# TopLevel.net
KiCad netlist of a schematic drawn in Altium Designer
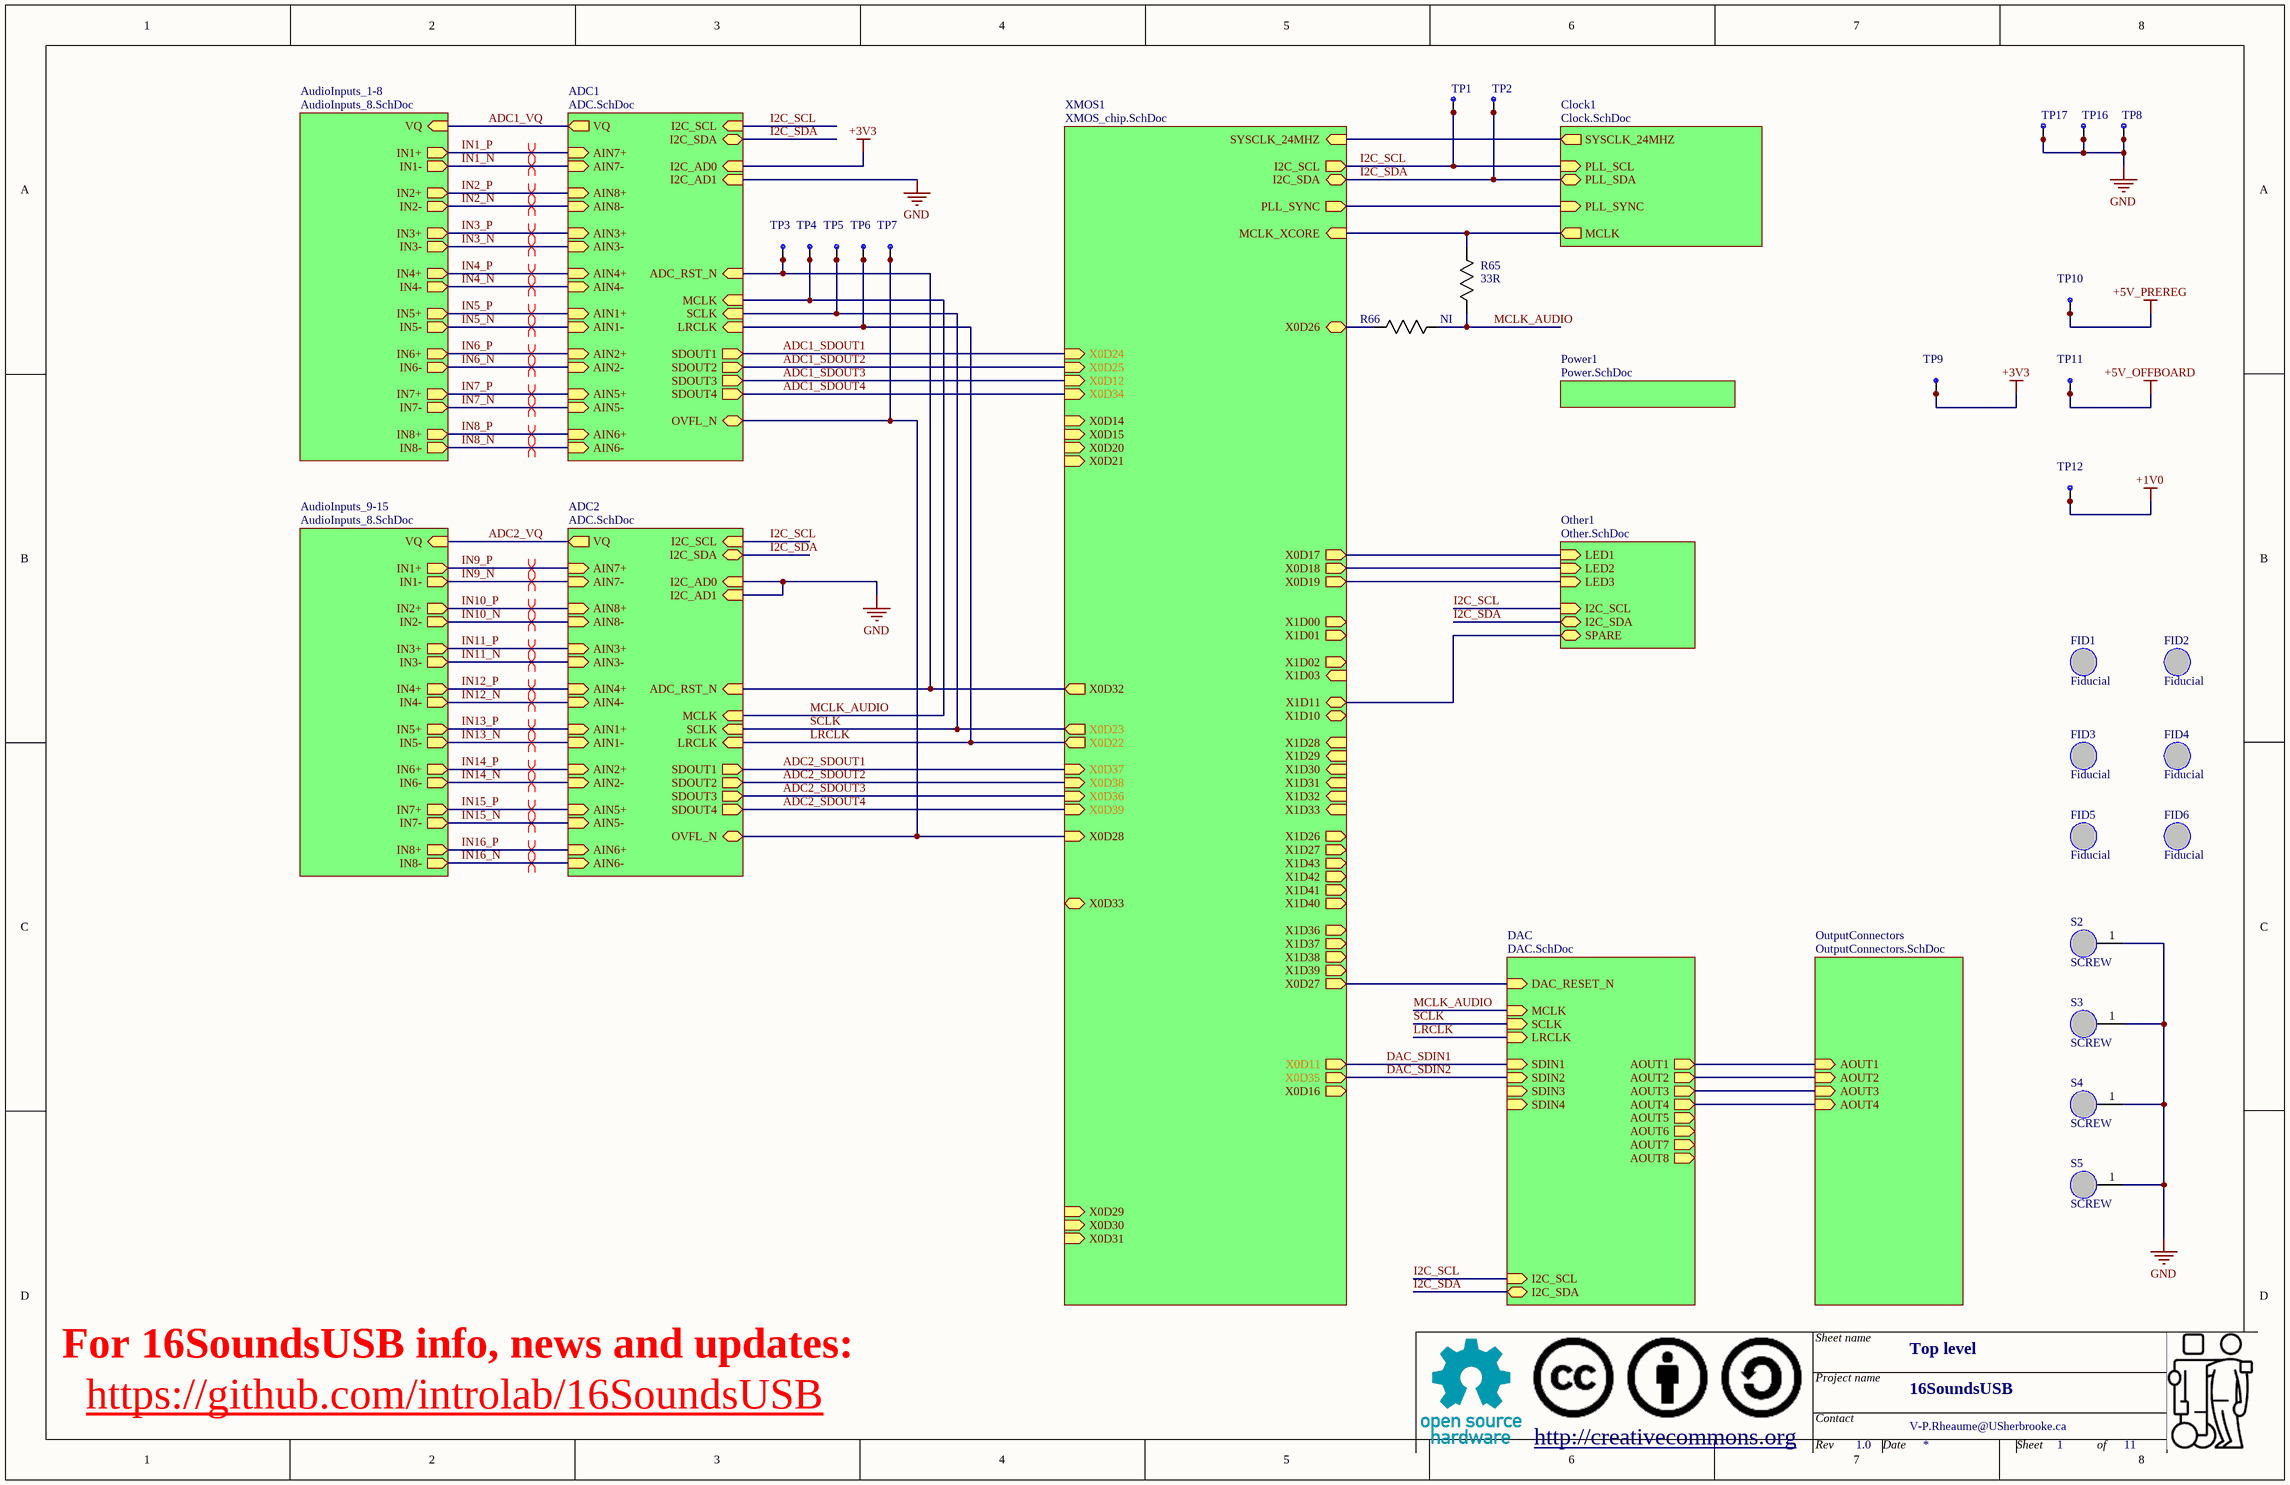
[diagram p0: TopLevel.SchDoc]

(export (version "E")
  (design (tool "Eeschema 10.0.6"))
  (components
    (comp (ref "FID1")
      (value "Fiducial")
      (footprint "FIDUCIAL")
      (libsource (lib "INTER_2014") (part "Fiducial"))
    )
    (comp (ref "FID2")
      (value "Fiducial")
      (footprint "FIDUCIAL")
      (libsource (lib "INTER_2014") (part "Fiducial"))
    )
    (comp (ref "FID3")
      (value "Fiducial")
      (footprint "FIDUCIAL")
      (libsource (lib "INTER_2014") (part "Fiducial"))
    )
    (comp (ref "FID4")
      (value "Fiducial")
      (footprint "FIDUCIAL")
      (libsource (lib "INTER_2014") (part "Fiducial"))
    )
    (comp (ref "FID5")
      (value "Fiducial")
      (footprint "FIDUCIAL")
      (libsource (lib "INTER_2014") (part "Fiducial"))
    )
    (comp (ref "FID6")
      (value "Fiducial")
      (footprint "FIDUCIAL")
      (libsource (lib "INTER_2014") (part "Fiducial"))
    )
    (comp (ref "R65")
      (value "33R")
      (footprint "0603")
      (description "Resistor")
      (fields (field (name "MFG") "Yageo"))
      (libsource (lib "INTER_2014") (part "Resistor"))
    )
    (comp (ref "R66")
      (value "Resistor")
      (footprint "0603")
      (fields (field (name "MFG") "Yageo") (field (name "NI") "NI"))
      (libsource (lib "INTER_2014") (part "Resistor"))
    )
    (comp (ref "S2")
      (value "SCREW")
      (footprint "SCREW_4_40")
      (description "Screw hole")
      (libsource (lib "INTER_2014") (part "SCREW"))
    )
    (comp (ref "S3")
      (value "SCREW")
      (footprint "SCREW_4_40")
      (description "Screw hole")
      (libsource (lib "INTER_2014") (part "SCREW"))
    )
    (comp (ref "S4")
      (value "SCREW")
      (footprint "SCREW_4_40")
      (description "Screw hole")
      (libsource (lib "INTER_2014") (part "SCREW"))
    )
    (comp (ref "S5")
      (value "SCREW")
      (footprint "SCREW_4_40")
      (description "Screw hole")
      (libsource (lib "INTER_2014") (part "SCREW"))
    )
    (comp (ref "TP1")
      (value "TESTPOINT")
      (footprint "0603")
      (description "Test point")
      (fields (field (name "MFG") "TE"))
      (libsource (lib "INTER_2014") (part "TESTPOINT"))
    )
    (comp (ref "TP2")
      (value "TESTPOINT")
      (footprint "0603")
      (description "Test point")
      (fields (field (name "MFG") "TE"))
      (libsource (lib "INTER_2014") (part "TESTPOINT"))
    )
    (comp (ref "TP3")
      (value "TESTPOINT")
      (footprint "0603")
      (description "Test point")
      (fields (field (name "MFG") "TE"))
      (libsource (lib "INTER_2014") (part "TESTPOINT"))
    )
    (comp (ref "TP4")
      (value "TESTPOINT")
      (footprint "0603")
      (description "Test point")
      (fields (field (name "MFG") "TE"))
      (libsource (lib "INTER_2014") (part "TESTPOINT"))
    )
    (comp (ref "TP5")
      (value "TESTPOINT")
      (footprint "0603")
      (description "Test point")
      (fields (field (name "MFG") "TE"))
      (libsource (lib "INTER_2014") (part "TESTPOINT"))
    )
    (comp (ref "TP6")
      (value "TESTPOINT")
      (footprint "0603")
      (description "Test point")
      (fields (field (name "MFG") "TE"))
      (libsource (lib "INTER_2014") (part "TESTPOINT"))
    )
    (comp (ref "TP7")
      (value "TESTPOINT")
      (footprint "0603")
      (description "Test point")
      (fields (field (name "MFG") "TE"))
      (libsource (lib "INTER_2014") (part "TESTPOINT"))
    )
    (comp (ref "TP8")
      (value "TESTPOINT")
      (footprint "1206")
      (description "Test point")
      (fields (field (name "MFG") "Harwin"))
      (libsource (lib "INTER_2014") (part "TESTPOINT"))
    )
    (comp (ref "TP9")
      (value "TESTPOINT")
      (footprint "0603")
      (description "Test point")
      (fields (field (name "MFG") "TE"))
      (libsource (lib "INTER_2014") (part "TESTPOINT"))
    )
    (comp (ref "TP10")
      (value "TESTPOINT")
      (footprint "0603")
      (description "Test point")
      (fields (field (name "MFG") "TE"))
      (libsource (lib "INTER_2014") (part "TESTPOINT"))
    )
    (comp (ref "TP11")
      (value "TESTPOINT")
      (footprint "0603")
      (description "Test point")
      (fields (field (name "MFG") "TE"))
      (libsource (lib "INTER_2014") (part "TESTPOINT"))
    )
    (comp (ref "TP12")
      (value "TESTPOINT")
      (footprint "0603")
      (description "Test point")
      (fields (field (name "MFG") "TE"))
      (libsource (lib "INTER_2014") (part "TESTPOINT"))
    )
    (comp (ref "TP16")
      (value "TESTPOINT")
      (footprint "1206")
      (description "Test point")
      (fields (field (name "MFG") "Harwin"))
      (libsource (lib "INTER_2014") (part "TESTPOINT"))
    )
    (comp (ref "TP17")
      (value "TESTPOINT")
      (footprint "1206")
      (description "Test point")
      (fields (field (name "MFG") "Harwin"))
      (libsource (lib "INTER_2014") (part "TESTPOINT"))
    )
  )
  (nets
    (net (code "1") (name "+1V0") (class "Default")
      (node (ref "TP12") (pin "1") (pintype "passive"))
      (node (ref "TP12") (pin "2") (pintype "passive"))
    )
    (net (code "2") (name "+3V3") (class "Default")
      (node (ref "TP9") (pin "1") (pintype "passive"))
      (node (ref "TP9") (pin "2") (pintype "passive"))
    )
    (net (code "3") (name "+5V_OFFBOARD") (class "Default")
      (node (ref "TP11") (pin "1") (pintype "passive"))
      (node (ref "TP11") (pin "2") (pintype "passive"))
    )
    (net (code "4") (name "+5V_PREREG") (class "Default")
      (node (ref "TP10") (pin "1") (pintype "passive"))
      (node (ref "TP10") (pin "2") (pintype "passive"))
    )
    (net (code "25") (name "/I2C_SCL") (class "Default")
      (node (ref "TP1") (pin "1") (pintype "passive"))
      (node (ref "TP1") (pin "2") (pintype "passive"))
    )
    (net (code "26") (name "/I2C_SDA") (class "Default")
      (node (ref "TP2") (pin "1") (pintype "passive"))
      (node (ref "TP2") (pin "2") (pintype "passive"))
    )
    (net (code "59") (name "/LRCLK") (class "Default")
      (node (ref "TP6") (pin "1") (pintype "passive"))
      (node (ref "TP6") (pin "2") (pintype "passive"))
    )
    (net (code "60") (name "/MCLK") (class "Default") (node (ref "R65") (pin "2") (pintype "passive")))
    (net (code "61") (name "/MCLK_AUDIO") (class "Default")
      (node (ref "R65") (pin "1") (pintype "passive"))
      (node (ref "R66") (pin "2") (pintype "passive"))
      (node (ref "TP4") (pin "1") (pintype "passive"))
      (node (ref "TP4") (pin "2") (pintype "passive"))
    )
    (net (code "62") (name "/OVFL_N") (class "Default")
      (node (ref "TP7") (pin "1") (pintype "passive"))
      (node (ref "TP7") (pin "2") (pintype "passive"))
    )
    (net (code "64") (name "/SCLK") (class "Default")
      (node (ref "TP5") (pin "1") (pintype "passive"))
      (node (ref "TP5") (pin "2") (pintype "passive"))
    )
    (net (code "77") (name "/X0D26") (class "Default") (node (ref "R66") (pin "1") (pintype "passive")))
    (net (code "82") (name "/X0D32") (class "Default")
      (node (ref "TP3") (pin "1") (pintype "passive"))
      (node (ref "TP3") (pin "2") (pintype "passive"))
    )
    (net (code "105") (name "GND") (class "Default")
      (node (ref "S2") (pin "1") (pintype "passive"))
      (node (ref "S3") (pin "1") (pintype "passive"))
      (node (ref "S4") (pin "1") (pintype "passive"))
      (node (ref "S5") (pin "1") (pintype "passive"))
      (node (ref "TP16") (pin "1") (pintype "passive"))
      (node (ref "TP16") (pin "2") (pintype "passive"))
      (node (ref "TP17") (pin "1") (pintype "passive"))
      (node (ref "TP17") (pin "2") (pintype "passive"))
      (node (ref "TP8") (pin "1") (pintype "passive"))
      (node (ref "TP8") (pin "2") (pintype "passive"))
    )
    (net (code "106") (name "unconnected-(FID1-Pad0)") (class "Default")
      (node (ref "FID1") (pin "0") (pintype "passive"))
    )
    (net (code "107") (name "unconnected-(FID2-Pad0)") (class "Default")
      (node (ref "FID2") (pin "0") (pintype "passive"))
    )
    (net (code "108") (name "unconnected-(FID3-Pad0)") (class "Default")
      (node (ref "FID3") (pin "0") (pintype "passive"))
    )
    (net (code "109") (name "unconnected-(FID4-Pad0)") (class "Default")
      (node (ref "FID4") (pin "0") (pintype "passive"))
    )
    (net (code "110") (name "unconnected-(FID5-Pad0)") (class "Default")
      (node (ref "FID5") (pin "0") (pintype "passive"))
    )
    (net (code "111") (name "unconnected-(FID6-Pad0)") (class "Default")
      (node (ref "FID6") (pin "0") (pintype "passive"))
    )
  )
)
